# DM1097_CM4.net
KiCad netlist of a schematic drawn in Altium Designer
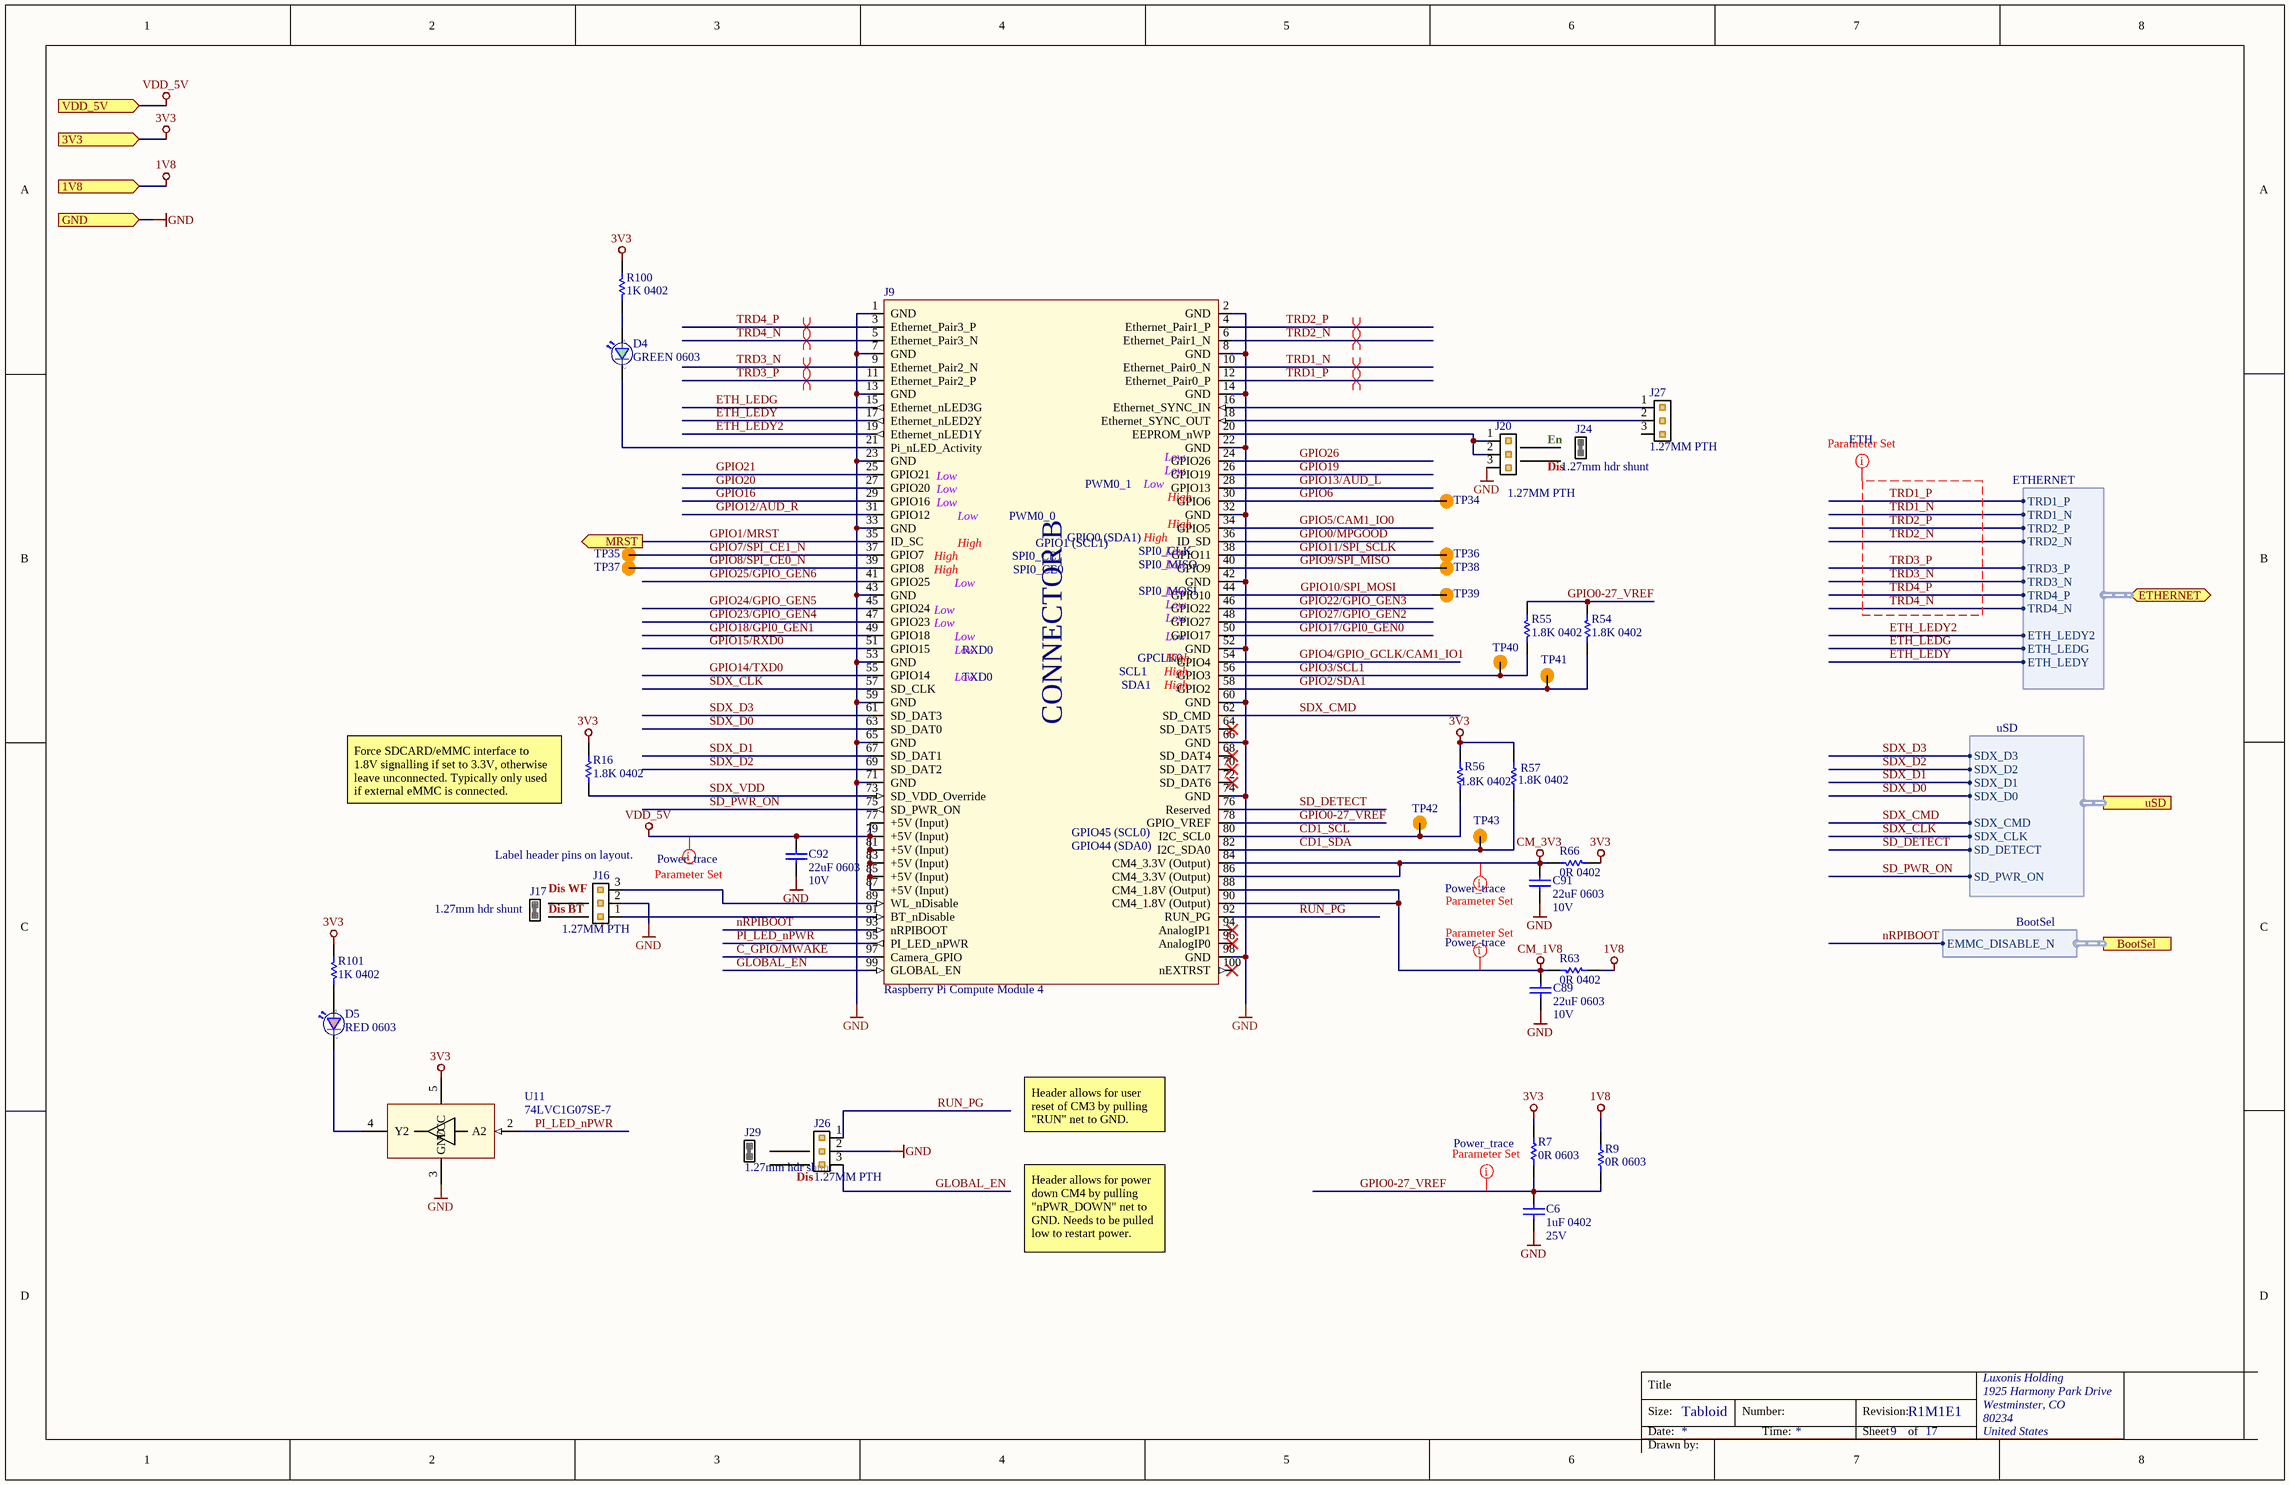
[diagram p0: DM1097_CM4.SchDoc]

(export (version "E")
  (design (tool "Eeschema 10.0.6"))
  (components
    (comp (ref "C6")
      (value "1uF 0402")
      (footprint "CAP_Altium_Vault_Generic:CAPC0402(1005)70_N")
      (description "CAP CER 1UF 25V X5R 0402 10%")
      (fields
        (field (name "TOLERANCE") "10%")
        (field (name "VOLTAGE") "25V")
        (field (name "VOLTAGE RATING") "25V")
      )
      (libsource (lib "LuxonisMaster") (part "GRM155R61E105KA12D"))
    )
    (comp (ref "C89")
      (value "22uF 0603")
      (footprint "CAP_Altium_Vault_Generic:CAPC0603(1608)100_N")
      (description "CAP CER 22UF 10V X5R 0603 20%")
      (fields (field (name "TOLERANCE") "20%") (field (name "VOLTAGE RATING") "10V"))
      (libsource (lib "LuxonisMaster") (part "GRM188R61A226ME15D"))
    )
    (comp (ref "C91")
      (value "22uF 0603")
      (footprint "CAP_Altium_Vault_Generic:CAPC0603(1608)100_N")
      (description "CAP CER 22UF 10V X5R 0603 20%")
      (fields (field (name "TOLERANCE") "20%") (field (name "VOLTAGE RATING") "10V"))
      (libsource (lib "LuxonisMaster") (part "GRM188R61A226ME15D"))
    )
    (comp (ref "C92")
      (value "22uF 0603")
      (footprint "CAP_Altium_Vault_Generic:CAPC0603(1608)100_N")
      (description "CAP CER 22UF 10V X5R 0603 20%")
      (fields (field (name "TOLERANCE") "20%") (field (name "VOLTAGE RATING") "10V"))
      (libsource (lib "LuxonisMaster") (part "GRM188R61A226ME15D"))
    )
    (comp (ref "D4")
      (value "GREEN 0603")
      (footprint "LuxonisMaster:SML_D1xx8W")
      (description "LED GREEN DIFFUSED 0603 SMD Green 572nm LED Indication - Discrete 2.2V 0603 (1608 Metric)")
      (fields (field (name "MANUFACTURER") "Rohm") (field (name "MANUFACTURER PART NUMBER") "SML-D12M8WT86"))
      (libsource (lib "LuxonisMaster") (part "SML-D12M8WT86"))
    )
    (comp (ref "D5")
      (value "RED 0603")
      (footprint "LuxonisMaster:SML_D1xx8W")
      (description "LED RED DIFFUSED 0603 SMD Red 620nm LED Indication - Discrete 2.2V 0603 (1608 Metric)")
      (libsource (lib "LuxonisMaster") (part "SML-D12U8WT86"))
    )
    (comp (ref "J9")
      (value "Raspberry Pi Compute Module 4")
      (footprint "CM4-Connector-B")
      (description "Raspberry Pi Compute Module 4 Hirose connector B")
      (libsource (lib "DM1097_SchLib") (part "CM4_CONNECTOR_B"))
    )
    (comp (ref "J16")
      (value "1.27MM PTH")
      (footprint "LuxonisMaster:GRPB031VWVN-RC")
      (description "CONN HEADER VERT 3POS 1.27MM")
      (libsource (lib "") (part "GRPB031VWVN-RC_2"))
    )
    (comp (ref "J17")
      (value "1.27mm hdr shunt")
      (footprint "LuxonisMaster:M50-1900005")
      (description "CONN SHUNT 1.27MM BLACK")
      (libsource (lib "LuxonisMaster") (part "M50-1900005"))
    )
    (comp (ref "J20")
      (value "1.27MM PTH")
      (footprint "LuxonisMaster:GRPB031VWVN-RC")
      (description "CONN HEADER VERT 3POS 1.27MM")
      (libsource (lib "LuxonisMaster") (part "GRPB031VWVN-RC"))
    )
    (comp (ref "J24")
      (value "1.27mm hdr shunt")
      (footprint "LuxonisMaster:M50-1900005")
      (description "CONN SHUNT 1.27MM BLACK")
      (libsource (lib "") (part "M50-1900005_1"))
    )
    (comp (ref "J26")
      (value "1.27MM PTH")
      (footprint "LuxonisMaster:GRPB031VWVN-RC")
      (description "CONN HEADER VERT 3POS 1.27MM")
      (libsource (lib "") (part "GRPB031VWVN-RC_1"))
    )
    (comp (ref "J27")
      (value "1.27MM PTH")
      (footprint "LuxonisMaster:GRPB031VWVN-RC")
      (description "CONN HEADER VERT 3POS 1.27MM")
      (libsource (lib "LuxonisMaster") (part "GRPB031VWVN-RC"))
    )
    (comp (ref "J29")
      (value "1.27mm hdr shunt")
      (footprint "LuxonisMaster:M50-1900005")
      (description "CONN SHUNT 1.27MM BLACK")
      (libsource (lib "LuxonisMaster") (part "M50-1900005"))
    )
    (comp (ref "R7")
      (value "0R 0603")
      (footprint "RES_Altium_Vault_Generic:RESC0603(1608)_N")
      (fields (field (name "TOLERANCE") "5%"))
      (libsource (lib "LuxonisMaster") (part "CRCW06030000Z0EA"))
    )
    (comp (ref "R9")
      (value "0R 0603")
      (footprint "RES_Altium_Vault_Generic:RESC0603(1608)_N")
      (fields (field (name "TOLERANCE") "5%"))
      (libsource (lib "LuxonisMaster") (part "CRCW06030000Z0EA"))
    )
    (comp (ref "R16")
      (value "1.8K 0402")
      (footprint "RES_Altium_Vault_Generic:RESC0402(1005)_N")
      (description "RES SMD 1.8K OHM 1% 1/16W 0402")
      (fields (field (name "TOLERANCE") "1%"))
      (libsource (lib "LuxonisMaster") (part "RC0402FR-071K8L"))
    )
    (comp (ref "R54")
      (value "1.8K 0402")
      (footprint "RES_Altium_Vault_Generic:RESC0402(1005)_N")
      (description "RES SMD 1.8K OHM 1% 1/16W 0402")
      (fields (field (name "TOLERANCE") "1%"))
      (libsource (lib "LuxonisMaster") (part "RC0402FR-071K8L"))
    )
    (comp (ref "R55")
      (value "1.8K 0402")
      (footprint "RES_Altium_Vault_Generic:RESC0402(1005)_N")
      (description "RES SMD 1.8K OHM 1% 1/16W 0402")
      (fields (field (name "TOLERANCE") "1%"))
      (libsource (lib "LuxonisMaster") (part "RC0402FR-071K8L"))
    )
    (comp (ref "R56")
      (value "1.8K 0402")
      (footprint "RES_Altium_Vault_Generic:RESC0402(1005)_N")
      (description "RES SMD 1.8K OHM 1% 1/16W 0402")
      (fields (field (name "TOLERANCE") "1%"))
      (libsource (lib "LuxonisMaster") (part "RC0402FR-071K8L"))
    )
    (comp (ref "R57")
      (value "1.8K 0402")
      (footprint "RES_Altium_Vault_Generic:RESC0402(1005)_N")
      (description "RES SMD 1.8K OHM 1% 1/16W 0402")
      (fields (field (name "TOLERANCE") "1%"))
      (libsource (lib "LuxonisMaster") (part "RC0402FR-071K8L"))
    )
    (comp (ref "R63")
      (value "0R 0402")
      (footprint "RES_Altium_Vault_Generic:RESC0402(1005)_N")
      (description "RES SMD 0 OHM JUMPER 1/16W 0402")
      (fields (field (name "TOLERANCE") "5%"))
      (libsource (lib "LuxonisMaster") (part "CRCW04020000Z0ED"))
    )
    (comp (ref "R66")
      (value "0R 0402")
      (footprint "RES_Altium_Vault_Generic:RESC0402(1005)_N")
      (description "RES SMD 0 OHM JUMPER 1/16W 0402")
      (fields (field (name "TOLERANCE") "5%"))
      (libsource (lib "LuxonisMaster") (part "CRCW04020000Z0ED"))
    )
    (comp (ref "R100")
      (value "1K 0402")
      (footprint "RES_Altium_Vault_Generic:RESC0402(1005)_N")
      (fields (field (name "TOLERANCE") "1%"))
      (libsource (lib "LuxonisMaster") (part "RC0402FR-071KL"))
    )
    (comp (ref "R101")
      (value "1K 0402")
      (footprint "RES_Altium_Vault_Generic:RESC0402(1005)_N")
      (fields (field (name "TOLERANCE") "1%"))
      (libsource (lib "LuxonisMaster") (part "RC0402FR-071KL"))
    )
    (comp (ref "TP34")
      (value "TP100_200_NS")
      (footprint "LuxonisMaster:TP100_200_NS")
      (libsource (lib "LuxonisMaster") (part "TEST_POINT"))
    )
    (comp (ref "TP35")
      (value "TP100_200_NS")
      (footprint "LuxonisMaster:TP100_200_NS")
      (libsource (lib "LuxonisMaster") (part "TEST_POINT"))
    )
    (comp (ref "TP36")
      (value "TP100_200_NS")
      (footprint "LuxonisMaster:TP100_200_NS")
      (libsource (lib "LuxonisMaster") (part "TEST_POINT"))
    )
    (comp (ref "TP37")
      (value "TP100_200_NS")
      (footprint "LuxonisMaster:TP100_200_NS")
      (libsource (lib "LuxonisMaster") (part "TEST_POINT"))
    )
    (comp (ref "TP38")
      (value "TP100_200_NS")
      (footprint "LuxonisMaster:TP100_200_NS")
      (libsource (lib "LuxonisMaster") (part "TEST_POINT"))
    )
    (comp (ref "TP39")
      (value "TP100_200_NS")
      (footprint "LuxonisMaster:TP100_200_NS")
      (libsource (lib "LuxonisMaster") (part "TEST_POINT"))
    )
    (comp (ref "TP40")
      (value "TP100_200_NS")
      (footprint "LuxonisMaster:TP100_200_NS")
      (libsource (lib "LuxonisMaster") (part "TEST_POINT"))
    )
    (comp (ref "TP41")
      (value "TP100_200_NS")
      (footprint "LuxonisMaster:TP100_200_NS")
      (libsource (lib "LuxonisMaster") (part "TEST_POINT"))
    )
    (comp (ref "TP42")
      (value "TP100_200_NS")
      (footprint "LuxonisMaster:TP100_200_NS")
      (libsource (lib "LuxonisMaster") (part "TEST_POINT"))
    )
    (comp (ref "TP43")
      (value "TP100_200_NS")
      (footprint "LuxonisMaster:TP100_200_NS")
      (libsource (lib "LuxonisMaster") (part "TEST_POINT"))
    )
    (comp (ref "U11")
      (value "74LVC1G07SE-7")
      (footprint "74LVC1G07SE-7")
      (description "SINGLE BUFFER/DRIVER WITH OPEN DRAIN OUTPUT")
      (libsource (lib "DM1097_SchLib") (part "74LVC1G07SE-7"))
    )
  )
  (nets
    (net (code "4") (name "/CD1_SCL") (class "Default")
      (node (ref "J9") (pin "80") (pinfunction "I2C_SCL0_80") (pintype "passive"))
      (node (ref "R56") (pin "1") (pinfunction "1_1") (pintype "passive"))
      (node (ref "TP42") (pin "1") (pintype "passive"))
    )
    (net (code "5") (name "/CD1_SDA") (class "Default")
      (node (ref "J9") (pin "82") (pinfunction "I2C_SDA0_82") (pintype "passive"))
      (node (ref "R57") (pin "1") (pinfunction "1_1") (pintype "passive"))
      (node (ref "TP43") (pin "1") (pintype "passive"))
    )
    (net (code "6") (name "/C_GPIO{slash}MWAKE") (class "Default")
      (node (ref "J9") (pin "97") (pinfunction "Camera_GPIO_97") (pintype "passive"))
    )
    (net (code "7") (name "/ETH_LEDG") (class "Default")
      (node (ref "J9") (pin "15") (pinfunction "Ethernet_nLED3G_15") (pintype "output"))
    )
    (net (code "8") (name "/ETH_LEDY") (class "Default")
      (node (ref "J9") (pin "17") (pinfunction "Ethernet_nLED2Y_17") (pintype "output"))
    )
    (net (code "9") (name "/ETH_LEDY2") (class "Default")
      (node (ref "J9") (pin "19") (pinfunction "Ethernet_nLED1Y_19") (pintype "output"))
    )
    (net (code "10") (name "/GLOBAL_EN") (class "Default")
      (node (ref "J26") (pin "3") (pinfunction "3_3") (pintype "passive"))
      (node (ref "J9") (pin "99") (pinfunction "GLOBAL_EN_99") (pintype "input"))
    )
    (net (code "11") (name "/GPIO0-27_VREF") (class "Default")
      (node (ref "C6") (pin "2") (pinfunction "2_2") (pintype "passive"))
      (node (ref "J9") (pin "78") (pinfunction "GPIO_VREF_78") (pintype "power_in"))
      (node (ref "R54") (pin "2") (pinfunction "2_2") (pintype "passive"))
      (node (ref "R55") (pin "2") (pinfunction "2_2") (pintype "passive"))
      (node (ref "R7") (pin "1") (pinfunction "1_1") (pintype "passive"))
      (node (ref "R9") (pin "1") (pinfunction "1_1") (pintype "passive"))
    )
    (net (code "12") (name "/GPIO0{slash}MPGOOD") (class "Default")
      (node (ref "J9") (pin "36") (pinfunction "ID_SD_36") (pintype "passive"))
    )
    (net (code "13") (name "/GPIO1{slash}MRST") (class "Default")
      (node (ref "J9") (pin "35") (pinfunction "ID_SC_35") (pintype "passive"))
    )
    (net (code "14") (name "/GPIO2{slash}SDA1") (class "Default")
      (node (ref "J9") (pin "58") (pinfunction "GPIO2_58") (pintype "passive"))
      (node (ref "R54") (pin "1") (pinfunction "1_1") (pintype "passive"))
      (node (ref "TP41") (pin "1") (pintype "passive"))
    )
    (net (code "15") (name "/GPIO3{slash}SCL1") (class "Default")
      (node (ref "J9") (pin "56") (pinfunction "GPIO3_56") (pintype "passive"))
      (node (ref "R55") (pin "1") (pinfunction "1_1") (pintype "passive"))
      (node (ref "TP40") (pin "1") (pintype "passive"))
    )
    (net (code "16") (name "/GPIO4{slash}GPIO_GCLK{slash}CAM1_IO1") (class "Default")
      (node (ref "J9") (pin "54") (pinfunction "GPIO4_54") (pintype "passive"))
    )
    (net (code "17") (name "/GPIO5{slash}CAM1_IO0") (class "Default")
      (node (ref "J9") (pin "34") (pinfunction "GPIO5_34") (pintype "passive"))
    )
    (net (code "18") (name "/GPIO6") (class "Default")
      (node (ref "J9") (pin "30") (pinfunction "GPIO6_30") (pintype "passive"))
      (node (ref "TP34") (pin "1") (pintype "passive"))
    )
    (net (code "19") (name "/GPIO7{slash}SPI_CE1_N") (class "Default")
      (node (ref "J9") (pin "37") (pinfunction "GPIO7_37") (pintype "passive"))
      (node (ref "TP35") (pin "1") (pintype "passive"))
    )
    (net (code "20") (name "/GPIO8{slash}SPI_CE0_N") (class "Default")
      (node (ref "J9") (pin "39") (pinfunction "GPIO8_39") (pintype "passive"))
      (node (ref "TP37") (pin "1") (pintype "passive"))
    )
    (net (code "21") (name "/GPIO9{slash}SPI_MISO") (class "Default")
      (node (ref "J9") (pin "40") (pinfunction "GPIO9_40") (pintype "passive"))
      (node (ref "TP38") (pin "1") (pintype "passive"))
    )
    (net (code "22") (name "/GPIO10{slash}SPI_MOSI") (class "Default")
      (node (ref "J9") (pin "44") (pinfunction "GPIO10_44") (pintype "passive"))
      (node (ref "TP39") (pin "1") (pintype "passive"))
    )
    (net (code "23") (name "/GPIO11{slash}SPI_SCLK") (class "Default")
      (node (ref "J9") (pin "38") (pinfunction "GPIO11_38") (pintype "passive"))
      (node (ref "TP36") (pin "1") (pintype "passive"))
    )
    (net (code "24") (name "/GPIO12{slash}AUD_R") (class "Default")
      (node (ref "J9") (pin "31") (pinfunction "GPIO12_31") (pintype "passive"))
    )
    (net (code "25") (name "/GPIO13{slash}AUD_L") (class "Default")
      (node (ref "J9") (pin "28") (pinfunction "GPIO13_28") (pintype "passive"))
    )
    (net (code "26") (name "/GPIO14{slash}TXD0") (class "Default")
      (node (ref "J9") (pin "55") (pinfunction "GPIO14_55") (pintype "passive"))
    )
    (net (code "27") (name "/GPIO15{slash}RXD0") (class "Default")
      (node (ref "J9") (pin "51") (pinfunction "GPIO15_51") (pintype "passive"))
    )
    (net (code "28") (name "/GPIO16") (class "Default")
      (node (ref "J9") (pin "29") (pinfunction "GPIO16_29") (pintype "passive"))
    )
    (net (code "29") (name "/GPIO17{slash}GPI0_GEN0") (class "Default")
      (node (ref "J9") (pin "50") (pinfunction "GPIO17_50") (pintype "passive"))
    )
    (net (code "30") (name "/GPIO18{slash}GPI0_GEN1") (class "Default")
      (node (ref "J9") (pin "49") (pinfunction "GPIO18_49") (pintype "passive"))
    )
    (net (code "31") (name "/GPIO19") (class "Default")
      (node (ref "J9") (pin "26") (pinfunction "GPIO19_26") (pintype "passive"))
    )
    (net (code "32") (name "/GPIO20") (class "Default")
      (node (ref "J9") (pin "27") (pinfunction "GPIO20_27") (pintype "passive"))
    )
    (net (code "33") (name "/GPIO21") (class "Default")
      (node (ref "J9") (pin "25") (pinfunction "GPIO21_25") (pintype "passive"))
    )
    (net (code "34") (name "/GPIO22{slash}GPIO_GEN3") (class "Default")
      (node (ref "J9") (pin "46") (pinfunction "GPIO22_46") (pintype "passive"))
    )
    (net (code "35") (name "/GPIO23{slash}GPIO_GEN4") (class "Default")
      (node (ref "J9") (pin "47") (pinfunction "GPIO23_47") (pintype "passive"))
    )
    (net (code "36") (name "/GPIO24{slash}GPIO_GEN5") (class "Default")
      (node (ref "J9") (pin "45") (pinfunction "GPIO24_45") (pintype "passive"))
    )
    (net (code "37") (name "/GPIO25{slash}GPIO_GEN6") (class "Default")
      (node (ref "J9") (pin "41") (pinfunction "GPIO25_41") (pintype "passive"))
    )
    (net (code "38") (name "/GPIO26") (class "Default")
      (node (ref "J9") (pin "24") (pinfunction "GPIO26_24") (pintype "passive"))
    )
    (net (code "39") (name "/GPIO27{slash}GPIO_GEN2") (class "Default")
      (node (ref "J9") (pin "48") (pinfunction "GPIO27_48") (pintype "passive"))
    )
    (net (code "40") (name "/PI_LED_nPWR") (class "Default")
      (node (ref "J9") (pin "95") (pinfunction "PI_LED_nPWR_95") (pintype "output"))
      (node (ref "U11") (pin "2") (pinfunction "A2_2") (pintype "input"))
    )
    (net (code "41") (name "/RUN_PG") (class "Default")
      (node (ref "J26") (pin "1") (pinfunction "1_1") (pintype "passive"))
      (node (ref "J9") (pin "92") (pinfunction "RUN_PG_92") (pintype "passive"))
    )
    (net (code "42") (name "/SDX_CLK") (class "Default")
      (node (ref "J9") (pin "57") (pinfunction "SD_CLK_57") (pintype "passive"))
    )
    (net (code "43") (name "/SDX_CMD") (class "Default")
      (node (ref "J9") (pin "62") (pinfunction "SD_CMD_62") (pintype "passive"))
    )
    (net (code "44") (name "/SDX_D0") (class "Default")
      (node (ref "J9") (pin "63") (pinfunction "SD_DAT0_63") (pintype "passive"))
    )
    (net (code "45") (name "/SDX_D1") (class "Default")
      (node (ref "J9") (pin "67") (pinfunction "SD_DAT1_67") (pintype "passive"))
    )
    (net (code "46") (name "/SDX_D2") (class "Default")
      (node (ref "J9") (pin "69") (pinfunction "SD_DAT2_69") (pintype "passive"))
    )
    (net (code "47") (name "/SDX_D3") (class "Default")
      (node (ref "J9") (pin "61") (pinfunction "SD_DAT3_61") (pintype "passive"))
    )
    (net (code "48") (name "/SDX_VDD") (class "Default")
      (node (ref "J9") (pin "73") (pinfunction "SD_VDD_Override_73") (pintype "input"))
      (node (ref "R16") (pin "1") (pinfunction "1_1") (pintype "passive"))
    )
    (net (code "49") (name "/SD_DETECT") (class "Default")
      (node (ref "J9") (pin "76") (pinfunction "Reserved_76") (pintype "passive"))
    )
    (net (code "50") (name "/SD_PWR_ON") (class "Default")
      (node (ref "J9") (pin "75") (pinfunction "SD_PWR_ON_75") (pintype "output"))
    )
    (net (code "51") (name "/TRD1_N") (class "Default")
      (node (ref "J9") (pin "10") (pinfunction "Ethernet_Pair0_N_10") (pintype "passive"))
    )
    (net (code "52") (name "/TRD1_P") (class "Default")
      (node (ref "J9") (pin "12") (pinfunction "Ethernet_Pair0_P_12") (pintype "passive"))
    )
    (net (code "53") (name "/TRD2_N") (class "Default")
      (node (ref "J9") (pin "6") (pinfunction "Ethernet_Pair1_N_6") (pintype "passive"))
    )
    (net (code "54") (name "/TRD2_P") (class "Default")
      (node (ref "J9") (pin "4") (pinfunction "Ethernet_Pair1_P_4") (pintype "passive"))
    )
    (net (code "55") (name "/TRD3_N") (class "Default")
      (node (ref "J9") (pin "9") (pinfunction "Ethernet_Pair2_N_9") (pintype "passive"))
    )
    (net (code "56") (name "/TRD3_P") (class "Default")
      (node (ref "J9") (pin "11") (pinfunction "Ethernet_Pair2_P_11") (pintype "passive"))
    )
    (net (code "57") (name "/TRD4_N") (class "Default")
      (node (ref "J9") (pin "5") (pinfunction "Ethernet_Pair3_N_5") (pintype "passive"))
    )
    (net (code "58") (name "/TRD4_P") (class "Default")
      (node (ref "J9") (pin "3") (pinfunction "Ethernet_Pair3_P_3") (pintype "passive"))
    )
    (net (code "59") (name "/nRPIBOOT") (class "Default")
      (node (ref "J9") (pin "93") (pinfunction "nRPIBOOT_93") (pintype "input"))
    )
    (net (code "63") (name "1V8") (class "Default")
      (node (ref "R63") (pin "1") (pinfunction "1_1") (pintype "passive"))
      (node (ref "R9") (pin "2") (pinfunction "2_2") (pintype "passive"))
    )
    (net (code "64") (name "3V3") (class "Default")
      (node (ref "R100") (pin "2") (pinfunction "2_2") (pintype "passive"))
      (node (ref "R101") (pin "2") (pinfunction "2_2") (pintype "passive"))
      (node (ref "R16") (pin "2") (pinfunction "2_2") (pintype "passive"))
      (node (ref "R56") (pin "2") (pinfunction "2_2") (pintype "passive"))
      (node (ref "R57") (pin "2") (pinfunction "2_2") (pintype "passive"))
      (node (ref "R66") (pin "1") (pinfunction "1_1") (pintype "passive"))
      (node (ref "R7") (pin "2") (pinfunction "2_2") (pintype "passive"))
      (node (ref "U11") (pin "5") (pinfunction "VCC_5") (pintype "power_in"))
    )
    (net (code "65") (name "CM_1V8") (class "Default")
      (node (ref "C89") (pin "1") (pinfunction "1_1") (pintype "passive"))
      (node (ref "J9") (pin "88") (pinfunction "CM4_1.8V_(Output)_88") (pintype "power_in"))
      (node (ref "J9") (pin "90") (pinfunction "CM4_1.8V_(Output)_90") (pintype "power_in"))
      (node (ref "R63") (pin "2") (pinfunction "2_2") (pintype "passive"))
    )
    (net (code "66") (name "CM_3V3") (class "Default")
      (node (ref "C91") (pin "1") (pinfunction "1_1") (pintype "passive"))
      (node (ref "J9") (pin "84") (pinfunction "CM4_3.3V_(Output)_84") (pintype "power_in"))
      (node (ref "J9") (pin "86") (pinfunction "CM4_3.3V_(Output)_86") (pintype "power_in"))
      (node (ref "R66") (pin "2") (pinfunction "2_2") (pintype "passive"))
    )
    (net (code "67") (name "GND") (class "Default")
      (node (ref "C6") (pin "1") (pinfunction "1_1") (pintype "passive"))
      (node (ref "C89") (pin "2") (pinfunction "2_2") (pintype "passive"))
      (node (ref "C91") (pin "2") (pinfunction "2_2") (pintype "passive"))
      (node (ref "C92") (pin "2") (pinfunction "2_2") (pintype "passive"))
      (node (ref "J16") (pin "2") (pinfunction "2_2") (pintype "passive"))
      (node (ref "J20") (pin "3") (pinfunction "3_3") (pintype "passive"))
      (node (ref "J26") (pin "2") (pinfunction "2_2") (pintype "passive"))
      (node (ref "J9") (pin "1") (pinfunction "GND_1") (pintype "power_in"))
      (node (ref "J9") (pin "13") (pinfunction "GND_13") (pintype "power_in"))
      (node (ref "J9") (pin "14") (pinfunction "GND_14") (pintype "power_in"))
      (node (ref "J9") (pin "2") (pinfunction "GND_2") (pintype "power_in"))
      (node (ref "J9") (pin "22") (pinfunction "GND_22") (pintype "power_in"))
      (node (ref "J9") (pin "23") (pinfunction "GND_23") (pintype "power_in"))
      (node (ref "J9") (pin "32") (pinfunction "GND_32") (pintype "power_in"))
      (node (ref "J9") (pin "33") (pinfunction "GND_33") (pintype "power_in"))
      (node (ref "J9") (pin "42") (pinfunction "GND_42") (pintype "power_in"))
      (node (ref "J9") (pin "43") (pinfunction "GND_43") (pintype "power_in"))
      (node (ref "J9") (pin "52") (pinfunction "GND_52") (pintype "power_in"))
      (node (ref "J9") (pin "53") (pinfunction "GND_53") (pintype "power_in"))
      (node (ref "J9") (pin "59") (pinfunction "GND_59") (pintype "power_in"))
      (node (ref "J9") (pin "60") (pinfunction "GND_60") (pintype "power_in"))
      (node (ref "J9") (pin "65") (pinfunction "GND_65") (pintype "power_in"))
      (node (ref "J9") (pin "66") (pinfunction "GND_66") (pintype "power_in"))
      (node (ref "J9") (pin "7") (pinfunction "GND_7") (pintype "power_in"))
      (node (ref "J9") (pin "71") (pinfunction "GND_71") (pintype "power_in"))
      (node (ref "J9") (pin "74") (pinfunction "GND_74") (pintype "power_in"))
      (node (ref "J9") (pin "8") (pinfunction "GND_8") (pintype "power_in"))
      (node (ref "J9") (pin "98") (pinfunction "GND_98") (pintype "power_in"))
      (node (ref "U11") (pin "3") (pinfunction "GND_3") (pintype "power_in"))
    )
    (net (code "68") (name "Net-(D4-A)") (class "Default")
      (node (ref "D4") (pin "2") (pinfunction "A_2") (pintype "passive"))
      (node (ref "R100") (pin "1") (pinfunction "1_1") (pintype "passive"))
    )
    (net (code "69") (name "Net-(D4-C)") (class "Default")
      (node (ref "D4") (pin "1") (pinfunction "C_1") (pintype "passive"))
      (node (ref "J9") (pin "21") (pinfunction "Pi_nLED_Activity_21") (pintype "open_collector"))
    )
    (net (code "70") (name "Net-(D5-A)") (class "Default")
      (node (ref "D5") (pin "2") (pinfunction "A_2") (pintype "passive"))
      (node (ref "R101") (pin "1") (pinfunction "1_1") (pintype "passive"))
    )
    (net (code "71") (name "Net-(D5-C)") (class "Default")
      (node (ref "D5") (pin "1") (pinfunction "C_1") (pintype "passive"))
      (node (ref "U11") (pin "4") (pinfunction "Y2_4") (pintype "open_collector"))
    )
    (net (code "72") (name "Net-(J9-BT_nDisable)") (class "Default")
      (node (ref "J16") (pin "1") (pinfunction "1_1") (pintype "passive"))
      (node (ref "J9") (pin "91") (pinfunction "BT_nDisable_91") (pintype "input"))
    )
    (net (code "73") (name "Net-(J9-EEPROM_nWP)") (class "Default")
      (node (ref "J20") (pin "1") (pinfunction "1_1") (pintype "passive"))
      (node (ref "J20") (pin "2") (pinfunction "2_2") (pintype "passive"))
      (node (ref "J9") (pin "20") (pinfunction "EEPROM_nWP_20") (pintype "passive"))
    )
    (net (code "74") (name "Net-(J9-Ethernet_SYNC_IN)") (class "Default")
      (node (ref "J27") (pin "1") (pinfunction "1_1") (pintype "passive"))
      (node (ref "J9") (pin "16") (pinfunction "Ethernet_SYNC_IN_16") (pintype "input"))
    )
    (net (code "75") (name "Net-(J9-Ethernet_SYNC_OUT)") (class "Default")
      (node (ref "J27") (pin "2") (pinfunction "2_2") (pintype "passive"))
      (node (ref "J9") (pin "18") (pinfunction "Ethernet_SYNC_OUT_18") (pintype "input"))
    )
    (net (code "76") (name "Net-(J9-WL_nDisable)") (class "Default")
      (node (ref "J16") (pin "3") (pinfunction "3_3") (pintype "passive"))
      (node (ref "J9") (pin "89") (pinfunction "WL_nDisable_89") (pintype "input"))
    )
    (net (code "77") (name "VDD_5V") (class "Default")
      (node (ref "C92") (pin "1") (pinfunction "1_1") (pintype "passive"))
      (node (ref "J9") (pin "77") (pinfunction "+5V_(Input)_77") (pintype "power_in"))
      (node (ref "J9") (pin "79") (pinfunction "+5V_(Input)_79") (pintype "power_in"))
      (node (ref "J9") (pin "81") (pinfunction "+5V_(Input)_81") (pintype "power_in"))
      (node (ref "J9") (pin "83") (pinfunction "+5V_(Input)_83") (pintype "power_in"))
      (node (ref "J9") (pin "85") (pinfunction "+5V_(Input)_85") (pintype "power_in"))
      (node (ref "J9") (pin "87") (pinfunction "+5V_(Input)_87") (pintype "power_in"))
    )
    (net (code "78") (name "unconnected-(J9-AnalogIP0-Pad96)") (class "Default")
      (node (ref "J9") (pin "96") (pinfunction "AnalogIP0_96") (pintype "passive+no_connect"))
    )
    (net (code "79") (name "unconnected-(J9-AnalogIP1-Pad94)") (class "Default")
      (node (ref "J9") (pin "94") (pinfunction "AnalogIP1_94") (pintype "passive+no_connect"))
    )
    (net (code "80") (name "unconnected-(J9-SD_DAT4-Pad68)") (class "Default")
      (node (ref "J9") (pin "68") (pinfunction "SD_DAT4_68") (pintype "passive+no_connect"))
    )
    (net (code "81") (name "unconnected-(J9-SD_DAT5-Pad64)") (class "Default")
      (node (ref "J9") (pin "64") (pinfunction "SD_DAT5_64") (pintype "passive+no_connect"))
    )
    (net (code "82") (name "unconnected-(J9-SD_DAT6-Pad72)") (class "Default")
      (node (ref "J9") (pin "72") (pinfunction "SD_DAT6_72") (pintype "passive+no_connect"))
    )
    (net (code "83") (name "unconnected-(J9-SD_DAT7-Pad70)") (class "Default")
      (node (ref "J9") (pin "70") (pinfunction "SD_DAT7_70") (pintype "passive+no_connect"))
    )
    (net (code "84") (name "unconnected-(J9-nEXTRST-Pad100)") (class "Default")
      (node (ref "J9") (pin "100") (pinfunction "nEXTRST_100") (pintype "output+no_connect"))
    )
    (net (code "85") (name "unconnected-(J27-Pad3)") (class "Default")
      (node (ref "J27") (pin "3") (pinfunction "3_3") (pintype "passive"))
    )
  )
)
